# Sinaliza_o_Official.net
KiCad netlist of a schematic drawn in Altium Designer
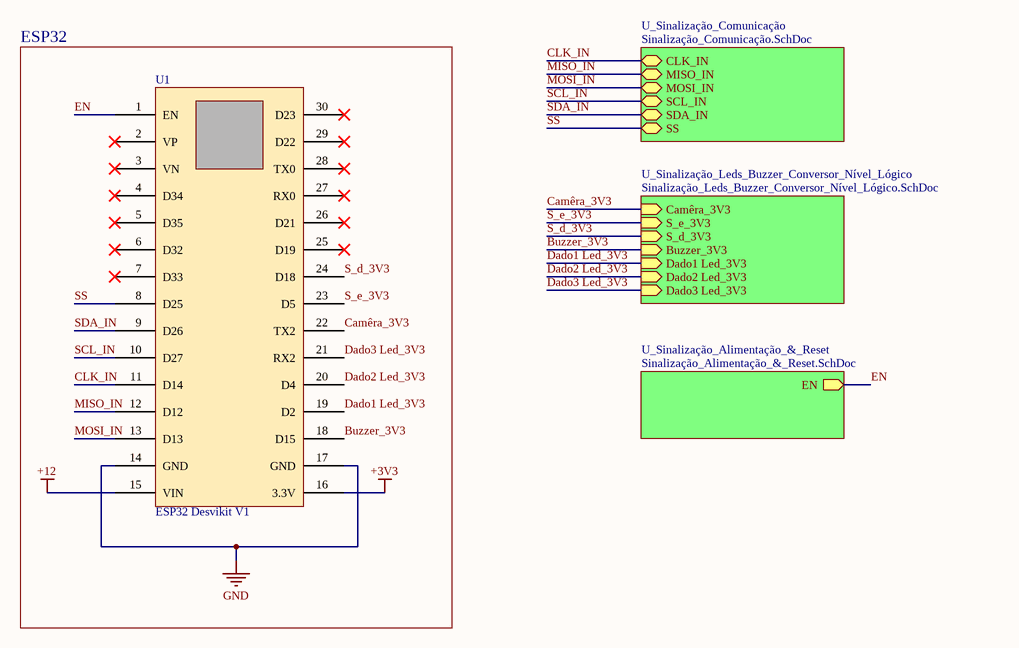
[diagram p0: Sinalização_Official.SchDoc]

(export (version "E")
  (design (tool "Eeschema 10.0.6"))
  (components
    (comp (ref "U1")
      (value "ESP32 Desvikit V1")
      (footprint "ESP32_Desvikit_v1")
      (description "microcontrolador com moculo bluethoth e wifi")
      (fields (field (name "Comment") "microcontrolador"))
      (libsource (lib "Sinalização_Official") (part "ESP32 Desvikit v1"))
    )
  )
  (nets
    (net (code "1") (name "+3V3") (class "Default")
      (node (ref "U1") (pin "16") (pinfunction "3.3V_16") (pintype "passive"))
    )
    (net (code "2") (name "+12") (class "Default")
      (node (ref "U1") (pin "15") (pinfunction "VIN_15") (pintype "passive"))
    )
    (net (code "3") (name "/Buzzer_3V3") (class "Default")
      (node (ref "U1") (pin "18") (pinfunction "D15_18") (pintype "passive"))
    )
    (net (code "4") (name "/CLK_IN") (class "Default")
      (node (ref "U1") (pin "11") (pinfunction "D14_11") (pintype "passive"))
    )
    (net (code "5") (name "/Camêra_3V3") (class "Default")
      (node (ref "U1") (pin "22") (pinfunction "TX2_22") (pintype "passive"))
    )
    (net (code "6") (name "/Dado1 Led_3V3") (class "Default")
      (node (ref "U1") (pin "19") (pinfunction "D2_19") (pintype "passive"))
    )
    (net (code "7") (name "/Dado2 Led_3V3") (class "Default")
      (node (ref "U1") (pin "20") (pinfunction "D4_20") (pintype "passive"))
    )
    (net (code "8") (name "/Dado3 Led_3V3") (class "Default")
      (node (ref "U1") (pin "21") (pinfunction "RX2_21") (pintype "passive"))
    )
    (net (code "9") (name "/EN") (class "Default")
      (node (ref "U1") (pin "1") (pinfunction "EN_1") (pintype "passive"))
    )
    (net (code "10") (name "/MISO_IN") (class "Default")
      (node (ref "U1") (pin "12") (pinfunction "D12_12") (pintype "passive"))
    )
    (net (code "11") (name "/MOSI_IN") (class "Default")
      (node (ref "U1") (pin "13") (pinfunction "D13_13") (pintype "passive"))
    )
    (net (code "12") (name "/SCL_IN") (class "Default")
      (node (ref "U1") (pin "10") (pinfunction "D27_10") (pintype "passive"))
    )
    (net (code "13") (name "/SDA_IN") (class "Default")
      (node (ref "U1") (pin "9") (pinfunction "D26_9") (pintype "passive"))
    )
    (net (code "14") (name "/SS") (class "Default")
      (node (ref "U1") (pin "8") (pinfunction "D25_8") (pintype "passive"))
    )
    (net (code "15") (name "/S_d_3V3") (class "Default")
      (node (ref "U1") (pin "24") (pinfunction "D18_24") (pintype "passive"))
    )
    (net (code "16") (name "/S_e_3V3") (class "Default")
      (node (ref "U1") (pin "23") (pinfunction "D5_23") (pintype "passive"))
    )
    (net (code "17") (name "GND") (class "Default")
      (node (ref "U1") (pin "14") (pinfunction "GND_14") (pintype "passive"))
      (node (ref "U1") (pin "17") (pinfunction "GND_17") (pintype "passive"))
    )
    (net (code "18") (name "unconnected-(U1-D19-Pad25)") (class "Default")
      (node (ref "U1") (pin "25") (pinfunction "D19_25") (pintype "passive+no_connect"))
    )
    (net (code "19") (name "unconnected-(U1-D21-Pad26)") (class "Default")
      (node (ref "U1") (pin "26") (pinfunction "D21_26") (pintype "passive+no_connect"))
    )
    (net (code "20") (name "unconnected-(U1-D22-Pad29)") (class "Default")
      (node (ref "U1") (pin "29") (pinfunction "D22_29") (pintype "passive+no_connect"))
    )
    (net (code "21") (name "unconnected-(U1-D23-Pad30)") (class "Default")
      (node (ref "U1") (pin "30") (pinfunction "D23_30") (pintype "passive+no_connect"))
    )
    (net (code "22") (name "unconnected-(U1-D32-Pad6)") (class "Default")
      (node (ref "U1") (pin "6") (pinfunction "D32_6") (pintype "passive+no_connect"))
    )
    (net (code "23") (name "unconnected-(U1-D33-Pad7)") (class "Default")
      (node (ref "U1") (pin "7") (pinfunction "D33_7") (pintype "passive+no_connect"))
    )
    (net (code "24") (name "unconnected-(U1-D34-Pad4)") (class "Default")
      (node (ref "U1") (pin "4") (pinfunction "D34_4") (pintype "passive+no_connect"))
    )
    (net (code "25") (name "unconnected-(U1-D35-Pad5)") (class "Default")
      (node (ref "U1") (pin "5") (pinfunction "D35_5") (pintype "passive+no_connect"))
    )
    (net (code "26") (name "unconnected-(U1-RX0-Pad27)") (class "Default")
      (node (ref "U1") (pin "27") (pinfunction "RX0_27") (pintype "passive+no_connect"))
    )
    (net (code "27") (name "unconnected-(U1-TX0-Pad28)") (class "Default")
      (node (ref "U1") (pin "28") (pinfunction "TX0_28") (pintype "passive+no_connect"))
    )
    (net (code "28") (name "unconnected-(U1-VN-Pad3)") (class "Default")
      (node (ref "U1") (pin "3") (pinfunction "VN_3") (pintype "passive+no_connect"))
    )
    (net (code "29") (name "unconnected-(U1-VP-Pad2)") (class "Default")
      (node (ref "U1") (pin "2") (pinfunction "VP_2") (pintype "passive+no_connect"))
    )
  )
)
